# DSO_Power.net
KiCad netlist of a schematic drawn in Altium Designer
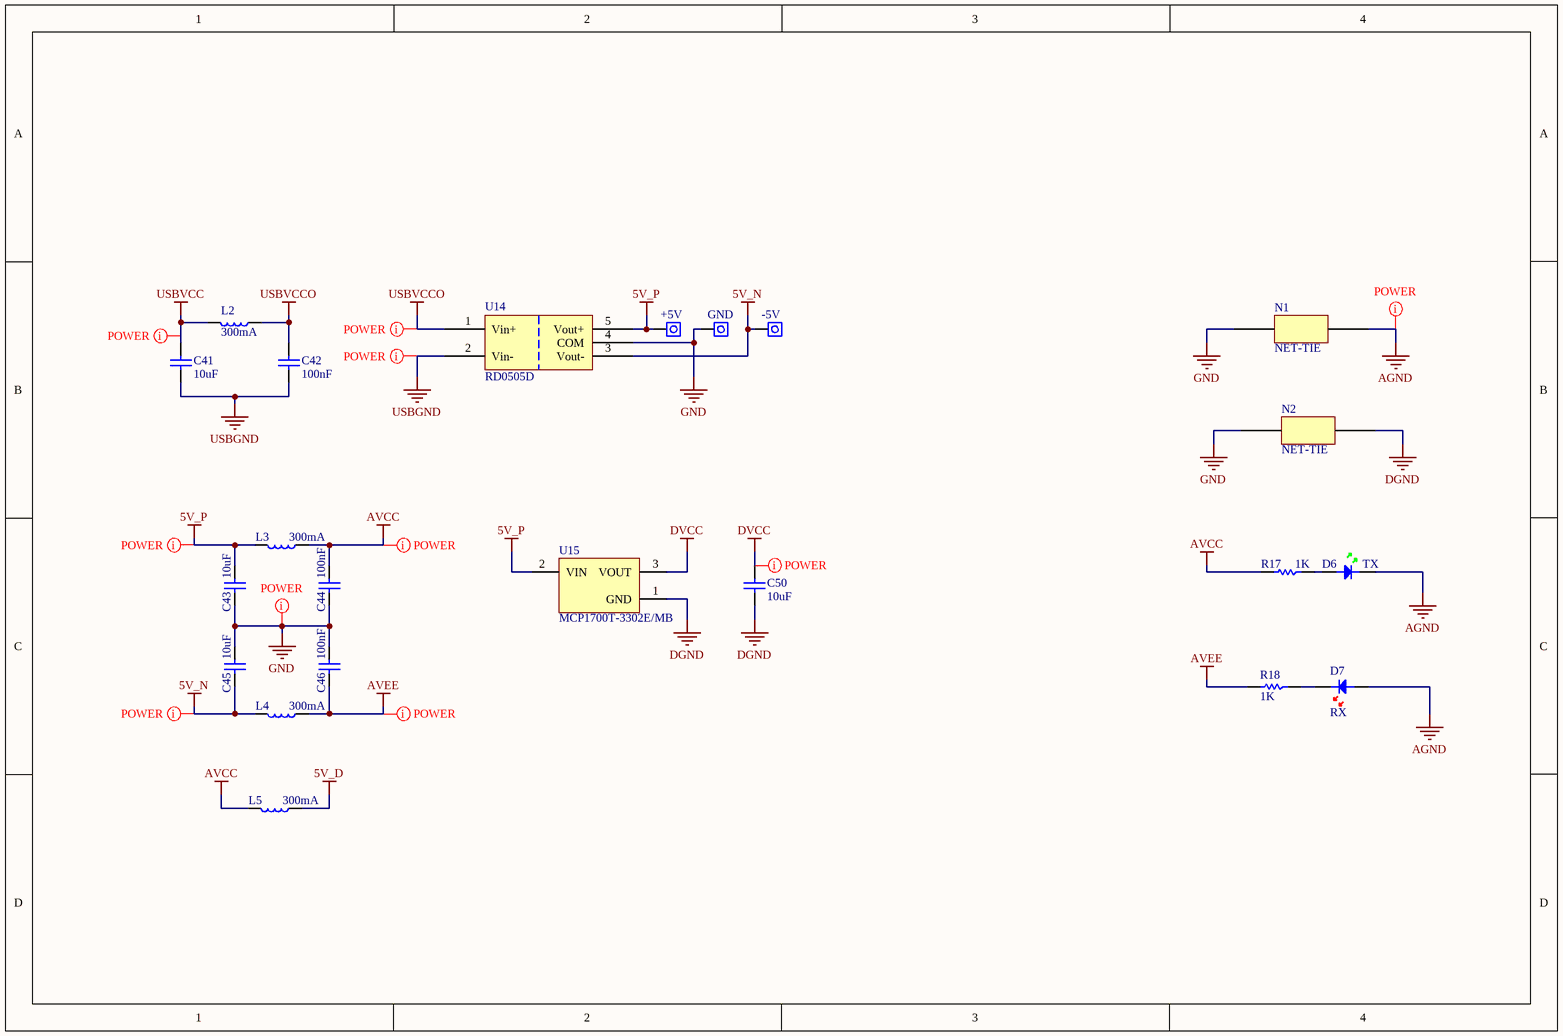
[diagram p0: DSO_Power.SchDoc]

(export (version "E")
  (design (tool "Eeschema 10.0.6"))
  (components
    (comp (ref "C41")
      (value "10uF")
      (footprint "0805")
      (description "Capacitor")
      (libsource (lib "DSO") (part "C"))
    )
    (comp (ref "C42")
      (value "100nF")
      (footprint "0805")
      (description "Capacitor")
      (libsource (lib "DSO") (part "C"))
    )
    (comp (ref "C43")
      (value "10uF")
      (footprint "0805")
      (description "Capacitor")
      (libsource (lib "DSO") (part "C"))
    )
    (comp (ref "C44")
      (value "100nF")
      (footprint "0805")
      (description "Capacitor")
      (libsource (lib "DSO") (part "C"))
    )
    (comp (ref "C45")
      (value "10uF")
      (footprint "0805")
      (description "Capacitor")
      (libsource (lib "DSO") (part "C"))
    )
    (comp (ref "C46")
      (value "100nF")
      (footprint "0805")
      (description "Capacitor")
      (libsource (lib "DSO") (part "C"))
    )
    (comp (ref "C50")
      (value "10uF")
      (footprint "0805C")
      (description "Capacitor")
      (fields (field (name "REVIEWED BY") "RM - 2018/08/05"))
      (libsource (lib "DSO") (part "C"))
    )
    (comp (ref "D6")
      (value "TX")
      (footprint "0805D-GREEN")
      (description "Light Emitting Diode")
      (fields (field (name "REVIEWED BY") "RM - 2018/08/05"))
      (libsource (lib "DSO") (part "LED GREEN"))
    )
    (comp (ref "D7")
      (value "RX")
      (footprint "0805D-RED")
      (description "Light Emitting Diode")
      (fields (field (name "REVIEWED BY") "RM - 2018/08/05"))
      (libsource (lib "DSO") (part "LED RED"))
    )
    (comp (ref "L2")
      (value "300mA")
      (footprint "0805")
      (description "Inductor")
      (fields (field (name "PUBLISHER") "Altium Limited"))
      (libsource (lib "DSO") (part "I"))
    )
    (comp (ref "L3")
      (value "300mA")
      (footprint "0805")
      (description "Inductor")
      (fields (field (name "PUBLISHER") "Altium Limited"))
      (libsource (lib "DSO") (part "I"))
    )
    (comp (ref "L4")
      (value "300mA")
      (footprint "0805")
      (description "Inductor")
      (fields (field (name "PUBLISHER") "Altium Limited"))
      (libsource (lib "DSO") (part "I"))
    )
    (comp (ref "L5")
      (value "300mA")
      (footprint "0805")
      (description "Inductor")
      (fields (field (name "PUBLISHER") "Altium Limited"))
      (libsource (lib "DSO") (part "I"))
    )
    (comp (ref "N1") (value "NET-TIE") (footprint "NET-TIE") (libsource (lib "RPOT") (part "NET-TIE")))
    (comp (ref "N2") (value "NET-TIE") (footprint "NET-TIE") (libsource (lib "RPOT") (part "NET-TIE")))
    (comp (ref "R17")
      (value "1K")
      (footprint "0805")
      (description "Resistor")
      (libsource (lib "DSO") (part "R"))
    )
    (comp (ref "R18")
      (value "1K")
      (footprint "0805")
      (description "Resistor")
      (libsource (lib "DSO") (part "R"))
    )
    (comp (ref "TP4")
      (value "+5V")
      (footprint "PIN 1.8mm")
      (description "Pad")
      (libsource (lib "DSO") (part "WIRE"))
    )
    (comp (ref "TP5")
      (value "GND")
      (footprint "PIN 1.8mm")
      (description "Pad")
      (libsource (lib "DSO") (part "WIRE"))
    )
    (comp (ref "TP6")
      (value "-5V")
      (footprint "PIN 1.8mm")
      (description "Pad")
      (libsource (lib "DSO") (part "WIRE"))
    )
    (comp (ref "U14")
      (value "RD0505D")
      (footprint "SIP_NMG")
      (description "(ADV) DC to DC converter 5V in +-5V out")
      (fields (field (name "REVIEWED BY") "RM - 2018/08/05"))
      (libsource (lib "DSO") (part "RD0505D"))
    )
    (comp (ref "U15")
      (value "MCP1700T-3302E/MB")
      (footprint "SOT89")
      (description "Low Quiescent Current LDO, 3-Pin SOT-89, Extended Temperature, Tape and Reel")
      (fields (field (name "REVIEWED BY") "RM - 2018/08/05"))
      (libsource (lib "DSO") (part "MCP1700T"))
    )
  )
  (nets
    (net (code "1") (name "5V_D") (class "Default")
      (node (ref "L5") (pin "1") (pinfunction "1_1") (pintype "passive"))
    )
    (net (code "2") (name "5V_N") (class "Default")
      (node (ref "C45") (pin "2") (pinfunction "2_2") (pintype "passive"))
      (node (ref "L4") (pin "2") (pinfunction "2_2") (pintype "passive"))
      (node (ref "TP6") (pin "1") (pintype "passive"))
      (node (ref "U14") (pin "3") (pinfunction "Vout-_3") (pintype "passive"))
    )
    (net (code "3") (name "5V_P") (class "Default")
      (node (ref "C43") (pin "1") (pinfunction "1_1") (pintype "passive"))
      (node (ref "L3") (pin "2") (pinfunction "2_2") (pintype "passive"))
      (node (ref "TP4") (pin "1") (pintype "passive"))
      (node (ref "U14") (pin "5") (pinfunction "Vout+_5") (pintype "passive"))
      (node (ref "U15") (pin "2") (pinfunction "VIN_2") (pintype "power_in"))
    )
    (net (code "4") (name "AGND") (class "Default")
      (node (ref "D6") (pin "K") (pinfunction "K_K") (pintype "passive"))
      (node (ref "D7") (pin "A") (pinfunction "A_A") (pintype "passive"))
      (node (ref "N1") (pin "1") (pinfunction "1_1") (pintype "passive"))
    )
    (net (code "5") (name "AVCC") (class "Default")
      (node (ref "C44") (pin "1") (pinfunction "1_1") (pintype "passive"))
      (node (ref "L3") (pin "1") (pinfunction "1_1") (pintype "passive"))
      (node (ref "L5") (pin "2") (pinfunction "2_2") (pintype "passive"))
      (node (ref "R17") (pin "2") (pintype "passive"))
    )
    (net (code "6") (name "AVEE") (class "Default")
      (node (ref "C46") (pin "2") (pinfunction "2_2") (pintype "passive"))
      (node (ref "L4") (pin "1") (pinfunction "1_1") (pintype "passive"))
      (node (ref "R18") (pin "2") (pintype "passive"))
    )
    (net (code "7") (name "DGND") (class "Default")
      (node (ref "C50") (pin "2") (pinfunction "2_2") (pintype "passive"))
      (node (ref "N2") (pin "1") (pinfunction "1_1") (pintype "passive"))
      (node (ref "U15") (pin "1") (pinfunction "GND_1") (pintype "power_in"))
    )
    (net (code "8") (name "DVCC") (class "Default")
      (node (ref "C50") (pin "1") (pinfunction "1_1") (pintype "passive"))
      (node (ref "U15") (pin "3") (pinfunction "VOUT_3") (pintype "power_in"))
    )
    (net (code "9") (name "GND") (class "Default")
      (node (ref "C43") (pin "2") (pinfunction "2_2") (pintype "passive"))
      (node (ref "C44") (pin "2") (pinfunction "2_2") (pintype "passive"))
      (node (ref "C45") (pin "1") (pinfunction "1_1") (pintype "passive"))
      (node (ref "C46") (pin "1") (pinfunction "1_1") (pintype "passive"))
      (node (ref "N1") (pin "0") (pinfunction "0_0") (pintype "passive"))
      (node (ref "N2") (pin "0") (pinfunction "0_0") (pintype "passive"))
      (node (ref "TP5") (pin "1") (pintype "passive"))
      (node (ref "U14") (pin "4") (pinfunction "COM_4") (pintype "passive"))
    )
    (net (code "10") (name "Net-(D6-PadA)") (class "Default")
      (node (ref "D6") (pin "A") (pinfunction "A_A") (pintype "passive"))
      (node (ref "R17") (pin "1") (pintype "passive"))
    )
    (net (code "11") (name "Net-(D7-PadK)") (class "Default")
      (node (ref "D7") (pin "K") (pinfunction "K_K") (pintype "passive"))
      (node (ref "R18") (pin "1") (pintype "passive"))
    )
    (net (code "12") (name "USBGND") (class "Default")
      (node (ref "C41") (pin "2") (pinfunction "2_2") (pintype "passive"))
      (node (ref "C42") (pin "2") (pinfunction "2_2") (pintype "passive"))
      (node (ref "U14") (pin "2") (pinfunction "Vin-_2") (pintype "passive"))
    )
    (net (code "13") (name "USBVCC") (class "Default")
      (node (ref "C41") (pin "1") (pinfunction "1_1") (pintype "passive"))
      (node (ref "L2") (pin "2") (pinfunction "2_2") (pintype "passive"))
    )
    (net (code "14") (name "USBVCCO") (class "Default")
      (node (ref "C42") (pin "1") (pinfunction "1_1") (pintype "passive"))
      (node (ref "L2") (pin "1") (pinfunction "1_1") (pintype "passive"))
      (node (ref "U14") (pin "1") (pinfunction "Vin+_1") (pintype "passive"))
    )
  )
)
